# GL852-1.net
KiCad netlist of a schematic drawn in Altium Designer
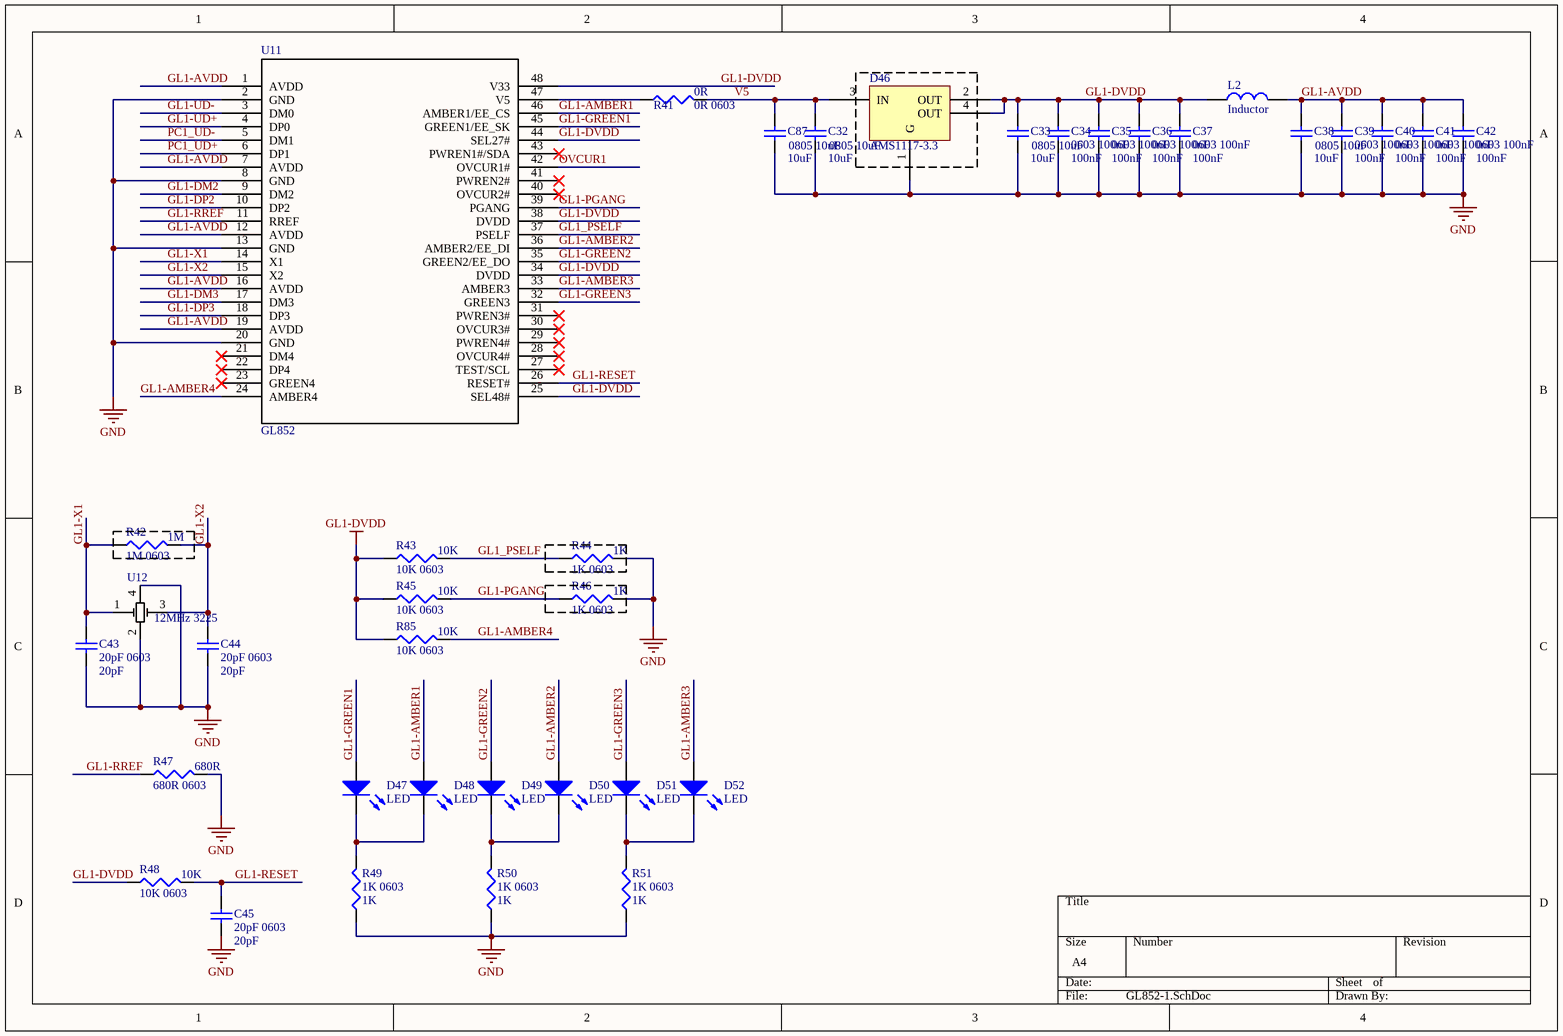
[diagram p0: GL852-1.SchDoc]

(export (version "E")
  (design (tool "Eeschema 10.0.6"))
  (components
    (comp (ref "C32")
      (value "0805 10uF")
      (footprint "C0805")
      (description "Capacitor (Semiconductor SIM Model)")
      (fields (field (name "ALTIUM_VALUE") "10uF") (field (name "PUBLISHER") "Altium Limited"))
      (libsource (lib "Miscellaneous Devices") (part "Cap Semi"))
    )
    (comp (ref "C33")
      (value "0805 10uF")
      (footprint "C0805")
      (description "Capacitor (Semiconductor SIM Model)")
      (fields (field (name "ALTIUM_VALUE") "10uF") (field (name "PUBLISHER") "Altium Limited"))
      (libsource (lib "Miscellaneous Devices") (part "Cap Semi"))
    )
    (comp (ref "C34")
      (value "0603 100nF")
      (footprint "C0603")
      (description "Capacitor (Semiconductor SIM Model)")
      (fields (field (name "ALTIUM_VALUE") "100nF") (field (name "PUBLISHER") "Altium Limited"))
      (libsource (lib "Miscellaneous Devices") (part "Cap Semi"))
    )
    (comp (ref "C35")
      (value "0603 100nF")
      (footprint "C0603")
      (description "Capacitor (Semiconductor SIM Model)")
      (fields (field (name "ALTIUM_VALUE") "100nF") (field (name "PUBLISHER") "Altium Limited"))
      (libsource (lib "Miscellaneous Devices") (part "Cap Semi"))
    )
    (comp (ref "C36")
      (value "0603 100nF")
      (footprint "C0603")
      (description "Capacitor (Semiconductor SIM Model)")
      (fields (field (name "ALTIUM_VALUE") "100nF") (field (name "PUBLISHER") "Altium Limited"))
      (libsource (lib "Miscellaneous Devices") (part "Cap Semi"))
    )
    (comp (ref "C37")
      (value "0603 100nF")
      (footprint "C0603")
      (description "Capacitor (Semiconductor SIM Model)")
      (fields (field (name "ALTIUM_VALUE") "100nF") (field (name "PUBLISHER") "Altium Limited"))
      (libsource (lib "Miscellaneous Devices") (part "Cap Semi"))
    )
    (comp (ref "C38")
      (value "0805 10uF")
      (footprint "C0805")
      (description "Capacitor (Semiconductor SIM Model)")
      (fields (field (name "ALTIUM_VALUE") "10uF") (field (name "PUBLISHER") "Altium Limited"))
      (libsource (lib "Miscellaneous Devices") (part "Cap Semi"))
    )
    (comp (ref "C39")
      (value "0603 100nF")
      (footprint "C0603")
      (description "Capacitor (Semiconductor SIM Model)")
      (fields (field (name "ALTIUM_VALUE") "100nF") (field (name "PUBLISHER") "Altium Limited"))
      (libsource (lib "Miscellaneous Devices") (part "Cap Semi"))
    )
    (comp (ref "C40")
      (value "0603 100nF")
      (footprint "C0603")
      (description "Capacitor (Semiconductor SIM Model)")
      (fields (field (name "ALTIUM_VALUE") "100nF") (field (name "PUBLISHER") "Altium Limited"))
      (libsource (lib "Miscellaneous Devices") (part "Cap Semi"))
    )
    (comp (ref "C41")
      (value "0603 100nF")
      (footprint "C0603")
      (description "Capacitor (Semiconductor SIM Model)")
      (fields (field (name "ALTIUM_VALUE") "100nF") (field (name "PUBLISHER") "Altium Limited"))
      (libsource (lib "Miscellaneous Devices") (part "Cap Semi"))
    )
    (comp (ref "C42")
      (value "0603 100nF")
      (footprint "C0603")
      (description "Capacitor (Semiconductor SIM Model)")
      (fields (field (name "ALTIUM_VALUE") "100nF") (field (name "PUBLISHER") "Altium Limited"))
      (libsource (lib "Miscellaneous Devices") (part "Cap Semi"))
    )
    (comp (ref "C43")
      (value "20pF 0603")
      (footprint "C0603")
      (description "Capacitor (Semiconductor SIM Model)")
      (fields (field (name "ALTIUM_VALUE") "20pF") (field (name "PUBLISHER") "Altium Limited"))
      (libsource (lib "Miscellaneous Devices") (part "Cap Semi"))
    )
    (comp (ref "C44")
      (value "20pF 0603")
      (footprint "C0603")
      (description "Capacitor (Semiconductor SIM Model)")
      (fields (field (name "ALTIUM_VALUE") "20pF") (field (name "PUBLISHER") "Altium Limited"))
      (libsource (lib "Miscellaneous Devices") (part "Cap Semi"))
    )
    (comp (ref "C45")
      (value "20pF 0603")
      (footprint "C0603")
      (description "Capacitor (Semiconductor SIM Model)")
      (fields (field (name "ALTIUM_VALUE") "20pF") (field (name "PUBLISHER") "Altium Limited"))
      (libsource (lib "Miscellaneous Devices") (part "Cap Semi"))
    )
    (comp (ref "C87")
      (value "0805 10uF")
      (footprint "C0805")
      (description "Capacitor (Semiconductor SIM Model)")
      (fields (field (name "ALTIUM_VALUE") "10uF") (field (name "PUBLISHER") "Altium Limited"))
      (libsource (lib "Miscellaneous Devices") (part "Cap Semi"))
    )
    (comp (ref "D46")
      (value "AMS1117-3.3")
      (footprint "SOT-223")
      (libsource (lib "MyLib") (part "AMS1117-3.3"))
    )
    (comp (ref "D47") (value "LED") (footprint "LED0603") (libsource (lib "Common Device") (part "LED")))
    (comp (ref "D48") (value "LED") (footprint "LED0603") (libsource (lib "Common Device") (part "LED")))
    (comp (ref "D49") (value "LED") (footprint "LED0603") (libsource (lib "Common Device") (part "LED")))
    (comp (ref "D50") (value "LED") (footprint "LED0603") (libsource (lib "Common Device") (part "LED")))
    (comp (ref "D51") (value "LED") (footprint "LED0603") (libsource (lib "Common Device") (part "LED")))
    (comp (ref "D52") (value "LED") (footprint "LED0603") (libsource (lib "Common Device") (part "LED")))
    (comp (ref "L2")
      (value "Inductor")
      (footprint "L0603")
      (libsource (lib "Common Device") (part "Inductor"))
    )
    (comp (ref "R41")
      (value "0R 0603")
      (footprint "R0603")
      (description "Resistor")
      (fields (field (name "ALTIUM_VALUE") "0R") (field (name "PUBLISHER") "Altium Limited"))
      (libsource (lib "Miscellaneous Devices") (part "Res3"))
    )
    (comp (ref "R42")
      (value "1M 0603")
      (footprint "R0603")
      (description "Resistor")
      (fields (field (name "ALTIUM_VALUE") "1M") (field (name "PUBLISHER") "Altium Limited"))
      (libsource (lib "Miscellaneous Devices") (part "Res3"))
    )
    (comp (ref "R43")
      (value "10K 0603")
      (footprint "R0603")
      (description "Resistor")
      (fields (field (name "ALTIUM_VALUE") "10K") (field (name "PUBLISHER") "Altium Limited"))
      (libsource (lib "Miscellaneous Devices") (part "Res3"))
    )
    (comp (ref "R44")
      (value "1K 0603")
      (footprint "R0603")
      (description "Resistor")
      (fields (field (name "ALTIUM_VALUE") "1K") (field (name "PUBLISHER") "Altium Limited"))
      (libsource (lib "Miscellaneous Devices") (part "Res3"))
    )
    (comp (ref "R45")
      (value "10K 0603")
      (footprint "R0603")
      (description "Resistor")
      (fields (field (name "ALTIUM_VALUE") "10K") (field (name "PUBLISHER") "Altium Limited"))
      (libsource (lib "Miscellaneous Devices") (part "Res3"))
    )
    (comp (ref "R46")
      (value "1K 0603")
      (footprint "R0603")
      (description "Resistor")
      (fields (field (name "ALTIUM_VALUE") "1K") (field (name "PUBLISHER") "Altium Limited"))
      (libsource (lib "Miscellaneous Devices") (part "Res3"))
    )
    (comp (ref "R47")
      (value "680R 0603")
      (footprint "R0603")
      (description "Resistor")
      (fields (field (name "ALTIUM_VALUE") "680R") (field (name "PUBLISHER") "Altium Limited"))
      (libsource (lib "Miscellaneous Devices") (part "Res3"))
    )
    (comp (ref "R48")
      (value "10K 0603")
      (footprint "R0603")
      (description "Resistor")
      (fields (field (name "ALTIUM_VALUE") "10K") (field (name "PUBLISHER") "Altium Limited"))
      (libsource (lib "Miscellaneous Devices") (part "Res3"))
    )
    (comp (ref "R49")
      (value "1K 0603")
      (footprint "R0603")
      (description "Resistor")
      (fields (field (name "ALTIUM_VALUE") "1K") (field (name "PUBLISHER") "Altium Limited"))
      (libsource (lib "Miscellaneous Devices") (part "Res3"))
    )
    (comp (ref "R50")
      (value "1K 0603")
      (footprint "R0603")
      (description "Resistor")
      (fields (field (name "ALTIUM_VALUE") "1K") (field (name "PUBLISHER") "Altium Limited"))
      (libsource (lib "Miscellaneous Devices") (part "Res3"))
    )
    (comp (ref "R51")
      (value "1K 0603")
      (footprint "R0603")
      (description "Resistor")
      (fields (field (name "ALTIUM_VALUE") "1K") (field (name "PUBLISHER") "Altium Limited"))
      (libsource (lib "Miscellaneous Devices") (part "Res3"))
    )
    (comp (ref "R85")
      (value "10K 0603")
      (footprint "R0603")
      (description "Resistor")
      (fields (field (name "ALTIUM_VALUE") "10K") (field (name "PUBLISHER") "Altium Limited"))
      (libsource (lib "Miscellaneous Devices") (part "Res3"))
    )
    (comp (ref "U11")
      (value "GL852")
      (footprint "qfp48-20-0909b")
      (description "Imported")
      (libsource (lib "USB-new-component") (part "GL852"))
    )
    (comp (ref "U12")
      (value "12MHz 3225")
      (footprint "XTAL-3225")
      (libsource (lib "XTAL3225") (part "Component_1"))
    )
  )
  (nets
    (net (code "1") (name "/GL1-AMBER1") (class "Default")
      (node (ref "D48") (pin "1") (pinfunction "A_1") (pintype "passive"))
      (node (ref "U11") (pin "46") (pinfunction "AMBER1/EE_CS_46") (pintype "passive"))
    )
    (net (code "2") (name "/GL1-AMBER2") (class "Default")
      (node (ref "D50") (pin "1") (pinfunction "A_1") (pintype "passive"))
      (node (ref "U11") (pin "36") (pinfunction "AMBER2/EE_DI_36") (pintype "passive"))
    )
    (net (code "3") (name "/GL1-AMBER3") (class "Default")
      (node (ref "D52") (pin "1") (pinfunction "A_1") (pintype "passive"))
      (node (ref "U11") (pin "33") (pinfunction "AMBER3_33") (pintype "passive"))
    )
    (net (code "4") (name "/GL1-AMBER4") (class "Default")
      (node (ref "R85") (pin "2") (pinfunction "2_2") (pintype "passive"))
      (node (ref "U11") (pin "24") (pinfunction "AMBER4_24") (pintype "passive"))
    )
    (net (code "5") (name "/GL1-AVDD") (class "Default")
      (node (ref "C38") (pin "2") (pinfunction "2_2") (pintype "passive"))
      (node (ref "C39") (pin "2") (pinfunction "2_2") (pintype "passive"))
      (node (ref "C40") (pin "2") (pinfunction "2_2") (pintype "passive"))
      (node (ref "C41") (pin "2") (pinfunction "2_2") (pintype "passive"))
      (node (ref "C42") (pin "2") (pinfunction "2_2") (pintype "passive"))
      (node (ref "L2") (pin "2") (pinfunction "2_2") (pintype "passive"))
      (node (ref "U11") (pin "1") (pinfunction "AVDD_1") (pintype "passive"))
      (node (ref "U11") (pin "12") (pinfunction "AVDD_12") (pintype "passive"))
      (node (ref "U11") (pin "16") (pinfunction "AVDD_16") (pintype "passive"))
      (node (ref "U11") (pin "19") (pinfunction "AVDD_19") (pintype "passive"))
      (node (ref "U11") (pin "7") (pinfunction "AVDD_7") (pintype "passive"))
    )
    (net (code "6") (name "/GL1-DM2") (class "Default")
      (node (ref "U11") (pin "9") (pinfunction "DM2_9") (pintype "passive"))
    )
    (net (code "7") (name "/GL1-DM3") (class "Default")
      (node (ref "U11") (pin "17") (pinfunction "DM3_17") (pintype "passive"))
    )
    (net (code "8") (name "/GL1-DP2") (class "Default")
      (node (ref "U11") (pin "10") (pinfunction "DP2_10") (pintype "passive"))
    )
    (net (code "9") (name "/GL1-DP3") (class "Default")
      (node (ref "U11") (pin "18") (pinfunction "DP3_18") (pintype "passive"))
    )
    (net (code "10") (name "/GL1-GREEN1") (class "Default")
      (node (ref "D47") (pin "1") (pinfunction "A_1") (pintype "passive"))
      (node (ref "U11") (pin "45") (pinfunction "GREEN1/EE_SK_45") (pintype "passive"))
    )
    (net (code "11") (name "/GL1-GREEN2") (class "Default")
      (node (ref "D49") (pin "1") (pinfunction "A_1") (pintype "passive"))
      (node (ref "U11") (pin "35") (pinfunction "GREEN2/EE_DO_35") (pintype "passive"))
    )
    (net (code "12") (name "/GL1-GREEN3") (class "Default")
      (node (ref "D51") (pin "1") (pinfunction "A_1") (pintype "passive"))
      (node (ref "U11") (pin "32") (pinfunction "GREEN3_32") (pintype "passive"))
    )
    (net (code "13") (name "/GL1-PGANG") (class "Default")
      (node (ref "R45") (pin "2") (pinfunction "2_2") (pintype "passive"))
      (node (ref "R46") (pin "1") (pinfunction "1_1") (pintype "passive"))
      (node (ref "U11") (pin "39") (pinfunction "PGANG_39") (pintype "passive"))
    )
    (net (code "14") (name "/GL1-RESET") (class "Default")
      (node (ref "C45") (pin "2") (pinfunction "2_2") (pintype "passive"))
      (node (ref "R48") (pin "2") (pinfunction "2_2") (pintype "passive"))
      (node (ref "U11") (pin "26") (pinfunction "RESET#_26") (pintype "passive"))
    )
    (net (code "15") (name "/GL1-RREF") (class "Default")
      (node (ref "R47") (pin "1") (pinfunction "1_1") (pintype "passive"))
      (node (ref "U11") (pin "11") (pinfunction "RREF_11") (pintype "passive"))
    )
    (net (code "16") (name "/GL1-UD+") (class "Default")
      (node (ref "U11") (pin "4") (pinfunction "DP0_4") (pintype "passive"))
    )
    (net (code "17") (name "/GL1-UD-") (class "Default")
      (node (ref "U11") (pin "3") (pinfunction "DM0_3") (pintype "passive"))
    )
    (net (code "18") (name "/GL1-X1") (class "Default")
      (node (ref "C43") (pin "2") (pinfunction "2_2") (pintype "passive"))
      (node (ref "R42") (pin "1") (pinfunction "1_1") (pintype "passive"))
      (node (ref "U11") (pin "14") (pinfunction "X1_14") (pintype "passive"))
      (node (ref "U12") (pin "1") (pinfunction "1_1") (pintype "passive"))
    )
    (net (code "19") (name "/GL1-X2") (class "Default")
      (node (ref "C44") (pin "2") (pinfunction "2_2") (pintype "passive"))
      (node (ref "R42") (pin "2") (pinfunction "2_2") (pintype "passive"))
      (node (ref "U11") (pin "15") (pinfunction "X2_15") (pintype "passive"))
      (node (ref "U12") (pin "3") (pinfunction "3_3") (pintype "passive"))
    )
    (net (code "20") (name "/GL1_PSELF") (class "Default")
      (node (ref "R43") (pin "2") (pinfunction "2_2") (pintype "passive"))
      (node (ref "R44") (pin "1") (pinfunction "1_1") (pintype "passive"))
      (node (ref "U11") (pin "37") (pinfunction "PSELF_37") (pintype "passive"))
    )
    (net (code "21") (name "/OVCUR1") (class "Default")
      (node (ref "U11") (pin "42") (pinfunction "OVCUR1#_42") (pintype "passive"))
    )
    (net (code "22") (name "/PC1_UD+") (class "Default")
      (node (ref "U11") (pin "6") (pinfunction "DP1_6") (pintype "passive"))
    )
    (net (code "23") (name "/PC1_UD-") (class "Default")
      (node (ref "U11") (pin "5") (pinfunction "DM1_5") (pintype "passive"))
    )
    (net (code "24") (name "/V5") (class "Default")
      (node (ref "C32") (pin "2") (pinfunction "2_2") (pintype "passive"))
      (node (ref "C87") (pin "2") (pinfunction "2_2") (pintype "passive"))
      (node (ref "D46") (pin "3") (pinfunction "IN_3") (pintype "passive"))
      (node (ref "R41") (pin "2") (pinfunction "2_2") (pintype "passive"))
    )
    (net (code "25") (name "GL1-DVDD") (class "Default")
      (node (ref "C33") (pin "2") (pinfunction "2_2") (pintype "passive"))
      (node (ref "C34") (pin "2") (pinfunction "2_2") (pintype "passive"))
      (node (ref "C35") (pin "2") (pinfunction "2_2") (pintype "passive"))
      (node (ref "C36") (pin "2") (pinfunction "2_2") (pintype "passive"))
      (node (ref "C37") (pin "2") (pinfunction "2_2") (pintype "passive"))
      (node (ref "D46") (pin "2") (pinfunction "OUT_2") (pintype "passive"))
      (node (ref "D46") (pin "4") (pinfunction "OUT_4") (pintype "passive"))
      (node (ref "L2") (pin "1") (pinfunction "1_1") (pintype "passive"))
      (node (ref "R43") (pin "1") (pinfunction "1_1") (pintype "passive"))
      (node (ref "R45") (pin "1") (pinfunction "1_1") (pintype "passive"))
      (node (ref "R48") (pin "1") (pinfunction "1_1") (pintype "passive"))
      (node (ref "R85") (pin "1") (pinfunction "1_1") (pintype "passive"))
      (node (ref "U11") (pin "25") (pinfunction "SEL48#_25") (pintype "passive"))
      (node (ref "U11") (pin "34") (pinfunction "DVDD_34") (pintype "passive"))
      (node (ref "U11") (pin "38") (pinfunction "DVDD_38") (pintype "passive"))
      (node (ref "U11") (pin "44") (pinfunction "SEL27#_44") (pintype "passive"))
      (node (ref "U11") (pin "48") (pinfunction "V33_48") (pintype "passive"))
    )
    (net (code "26") (name "GND") (class "Default")
      (node (ref "C32") (pin "1") (pinfunction "1_1") (pintype "passive"))
      (node (ref "C33") (pin "1") (pinfunction "1_1") (pintype "passive"))
      (node (ref "C34") (pin "1") (pinfunction "1_1") (pintype "passive"))
      (node (ref "C35") (pin "1") (pinfunction "1_1") (pintype "passive"))
      (node (ref "C36") (pin "1") (pinfunction "1_1") (pintype "passive"))
      (node (ref "C37") (pin "1") (pinfunction "1_1") (pintype "passive"))
      (node (ref "C38") (pin "1") (pinfunction "1_1") (pintype "passive"))
      (node (ref "C39") (pin "1") (pinfunction "1_1") (pintype "passive"))
      (node (ref "C40") (pin "1") (pinfunction "1_1") (pintype "passive"))
      (node (ref "C41") (pin "1") (pinfunction "1_1") (pintype "passive"))
      (node (ref "C42") (pin "1") (pinfunction "1_1") (pintype "passive"))
      (node (ref "C43") (pin "1") (pinfunction "1_1") (pintype "passive"))
      (node (ref "C44") (pin "1") (pinfunction "1_1") (pintype "passive"))
      (node (ref "C45") (pin "1") (pinfunction "1_1") (pintype "passive"))
      (node (ref "C87") (pin "1") (pinfunction "1_1") (pintype "passive"))
      (node (ref "D46") (pin "1") (pinfunction "G_1") (pintype "passive"))
      (node (ref "R44") (pin "2") (pinfunction "2_2") (pintype "passive"))
      (node (ref "R46") (pin "2") (pinfunction "2_2") (pintype "passive"))
      (node (ref "R47") (pin "2") (pinfunction "2_2") (pintype "passive"))
      (node (ref "R49") (pin "1") (pinfunction "1_1") (pintype "passive"))
      (node (ref "R50") (pin "1") (pinfunction "1_1") (pintype "passive"))
      (node (ref "R51") (pin "1") (pinfunction "1_1") (pintype "passive"))
      (node (ref "U11") (pin "13") (pinfunction "GND_13") (pintype "passive"))
      (node (ref "U11") (pin "2") (pinfunction "GND_2") (pintype "passive"))
      (node (ref "U11") (pin "20") (pinfunction "GND_20") (pintype "passive"))
      (node (ref "U11") (pin "8") (pinfunction "GND_8") (pintype "passive"))
      (node (ref "U12") (pin "2") (pinfunction "2_2") (pintype "passive"))
      (node (ref "U12") (pin "4") (pinfunction "4_4") (pintype "passive"))
    )
    (net (code "27") (name "Net-(D47-K)") (class "Default")
      (node (ref "D47") (pin "2") (pinfunction "K_2") (pintype "passive"))
      (node (ref "D48") (pin "2") (pinfunction "K_2") (pintype "passive"))
      (node (ref "R49") (pin "2") (pinfunction "2_2") (pintype "passive"))
    )
    (net (code "28") (name "Net-(D49-K)") (class "Default")
      (node (ref "D49") (pin "2") (pinfunction "K_2") (pintype "passive"))
      (node (ref "D50") (pin "2") (pinfunction "K_2") (pintype "passive"))
      (node (ref "R50") (pin "2") (pinfunction "2_2") (pintype "passive"))
    )
    (net (code "29") (name "Net-(D51-K)") (class "Default")
      (node (ref "D51") (pin "2") (pinfunction "K_2") (pintype "passive"))
      (node (ref "D52") (pin "2") (pinfunction "K_2") (pintype "passive"))
      (node (ref "R51") (pin "2") (pinfunction "2_2") (pintype "passive"))
    )
    (net (code "30") (name "Net-(U11-V5)") (class "Default")
      (node (ref "R41") (pin "1") (pinfunction "1_1") (pintype "passive"))
      (node (ref "U11") (pin "47") (pinfunction "V5_47") (pintype "passive"))
    )
    (net (code "31") (name "unconnected-(U11-DM4-Pad21)") (class "Default")
      (node (ref "U11") (pin "21") (pinfunction "DM4_21") (pintype "passive+no_connect"))
    )
    (net (code "32") (name "unconnected-(U11-DP4-Pad22)") (class "Default")
      (node (ref "U11") (pin "22") (pinfunction "DP4_22") (pintype "passive+no_connect"))
    )
    (net (code "33") (name "unconnected-(U11-GREEN4-Pad23)") (class "Default")
      (node (ref "U11") (pin "23") (pinfunction "GREEN4_23") (pintype "passive+no_connect"))
    )
    (net (code "34") (name "unconnected-(U11-OVCUR2#-Pad40)") (class "Default")
      (node (ref "U11") (pin "40") (pinfunction "OVCUR2#_40") (pintype "passive+no_connect"))
    )
    (net (code "35") (name "unconnected-(U11-OVCUR3#-Pad30)") (class "Default")
      (node (ref "U11") (pin "30") (pinfunction "OVCUR3#_30") (pintype "passive+no_connect"))
    )
    (net (code "36") (name "unconnected-(U11-OVCUR4#-Pad28)") (class "Default")
      (node (ref "U11") (pin "28") (pinfunction "OVCUR4#_28") (pintype "passive+no_connect"))
    )
    (net (code "37") (name "unconnected-(U11-PWREN1#{slash}SDA-Pad43)") (class "Default")
      (node (ref "U11") (pin "43") (pinfunction "PWREN1#/SDA_43") (pintype "passive+no_connect"))
    )
    (net (code "38") (name "unconnected-(U11-PWREN2#-Pad41)") (class "Default")
      (node (ref "U11") (pin "41") (pinfunction "PWREN2#_41") (pintype "passive+no_connect"))
    )
    (net (code "39") (name "unconnected-(U11-PWREN3#-Pad31)") (class "Default")
      (node (ref "U11") (pin "31") (pinfunction "PWREN3#_31") (pintype "passive+no_connect"))
    )
    (net (code "40") (name "unconnected-(U11-PWREN4#-Pad29)") (class "Default")
      (node (ref "U11") (pin "29") (pinfunction "PWREN4#_29") (pintype "passive+no_connect"))
    )
    (net (code "41") (name "unconnected-(U11-TEST{slash}SCL-Pad27)") (class "Default")
      (node (ref "U11") (pin "27") (pinfunction "TEST/SCL_27") (pintype "passive+no_connect"))
    )
  )
)
